# stm32f030f4p6-enc28j60.net
KiCad netlist of a schematic drawn in EAGLE
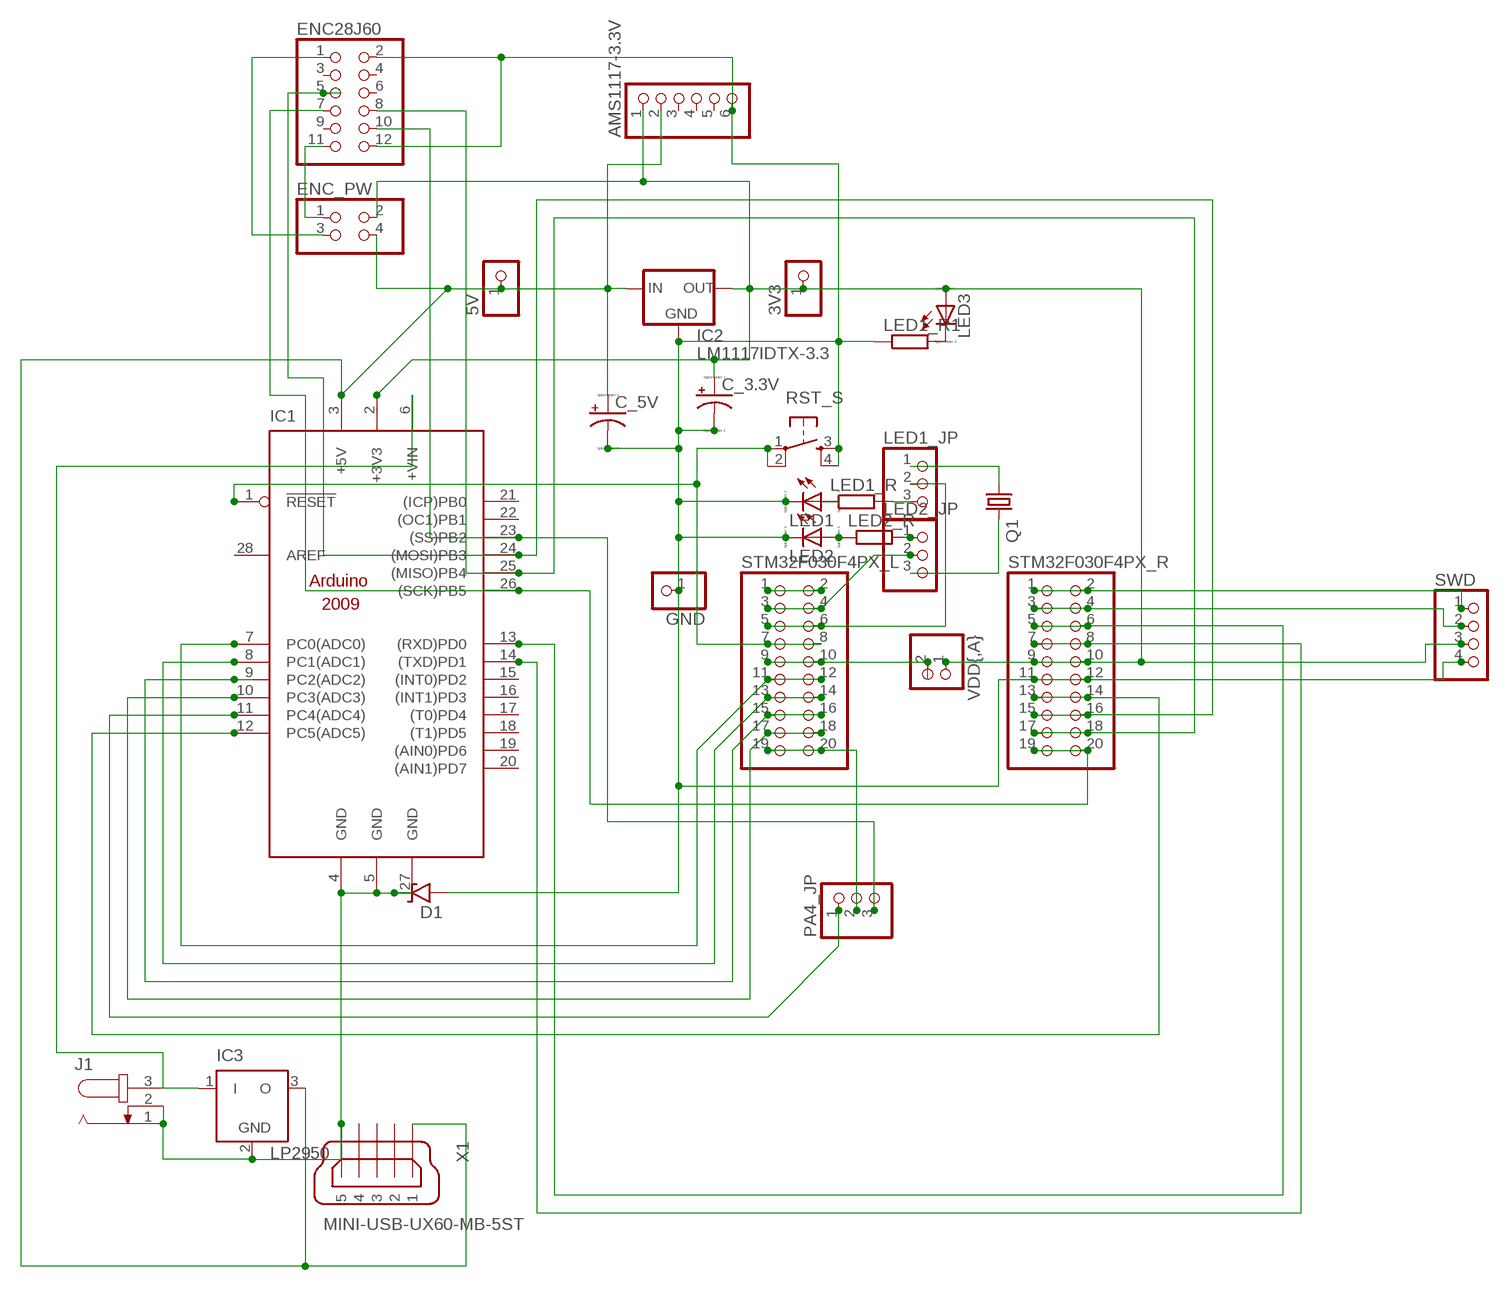
[diagram p0: schematic, sheet 1]

(export (version "E")
  (design (tool "Eeschema 10.0.6"))
  (components
    (comp (ref "3V3")
      (value "PINHD-1X1_2.00")
      (footprint "eagle-import:1X01M")
      (libsource (lib "eagle-import") (part "PINHD-1X1_2.00"))
    )
    (comp (ref "5V")
      (value "PINHD-1X1_2.00")
      (footprint "eagle-import:1X01M")
      (libsource (lib "eagle-import") (part "PINHD-1X1_2.00"))
    )
    (comp (ref "AMS1117-3.3V")
      (value "PINHD-1X06_2.54")
      (footprint "eagle-import:1X06")
      (libsource (lib "eagle-import") (part "PINHD-1X06_2.54"))
    )
    (comp (ref "C_3.3V")
      (value "CPOL-USE3.5-8")
      (footprint "eagle-import:E3,5-8")
      (libsource (lib "eagle-import") (part "CPOL-USE3.5-8"))
    )
    (comp (ref "C_5V")
      (value "CPOL-USE3.5-8")
      (footprint "eagle-import:E3,5-8")
      (libsource (lib "eagle-import") (part "CPOL-USE3.5-8"))
    )
    (comp (ref "D1")
      (value "1N9ZENER2")
      (footprint "eagle-import:DO35-2")
      (libsource (lib "eagle-import") (part "1N9ZENER2"))
    )
    (comp (ref "ENC28J60")
      (value "PINHD-2X6_2.54")
      (footprint "eagle-import:2X06")
      (libsource (lib "eagle-import") (part "PINHD-2X6_2.54"))
    )
    (comp (ref "ENC_PW")
      (value "PINHD-2X2_2.54")
      (footprint "eagle-import:2X02")
      (libsource (lib "eagle-import") (part "PINHD-2X2_2.54"))
    )
    (comp (ref "GND")
      (value "PINHD-1X1_2.00")
      (footprint "eagle-import:1X01M")
      (libsource (lib "eagle-import") (part "PINHD-1X1_2.00"))
    )
    (comp (ref "IC1")
      (value "ARDUINO2009_PIN_12")
      (footprint "eagle-import:ARDUINO2009_2")
      (libsource (lib "eagle-import") (part "ARDUINO2009_PIN_12"))
    )
    (comp (ref "IC2")
      (value "LM1117IDTX-3.3")
      (footprint "eagle-import:TO252")
      (libsource (lib "eagle-import") (part "LM1117IDTX-3.3"))
    )
    (comp (ref "IC3")
      (value "LP2950")
      (footprint "eagle-import:DPACK")
      (libsource (lib "eagle-import") (part "LP2950"))
    )
    (comp (ref "J1")
      (value "JACK-PLUG0")
      (footprint "eagle-import:SPC4077")
      (libsource (lib "eagle-import") (part "JACK-PLUG0"))
    )
    (comp (ref "LED1")
      (value "LED_ELD260")
      (footprint "eagle-import:LED_LD260")
      (libsource (lib "eagle-import") (part "LED_ELD260"))
    )
    (comp (ref "LED1_JP")
      (value "PINHD-1X3_2.54")
      (footprint "eagle-import:1X03")
      (libsource (lib "eagle-import") (part "PINHD-1X3_2.54"))
    )
    (comp (ref "LED1_R")
      (value "R-EU_0204/7")
      (footprint "eagle-import:0204_7")
      (libsource (lib "eagle-import") (part "R-EU_0204/7"))
    )
    (comp (ref "LED1_R1")
      (value "R-EU_0204/7")
      (footprint "eagle-import:0204_7")
      (libsource (lib "eagle-import") (part "R-EU_0204/7"))
    )
    (comp (ref "LED2")
      (value "LED_ELD260")
      (footprint "eagle-import:LED_LD260")
      (libsource (lib "eagle-import") (part "LED_ELD260"))
    )
    (comp (ref "LED2_JP")
      (value "PINHD-1X3_2.54")
      (footprint "eagle-import:1X03")
      (libsource (lib "eagle-import") (part "PINHD-1X3_2.54"))
    )
    (comp (ref "LED2_R")
      (value "R-EU_0204/7")
      (footprint "eagle-import:0204_7")
      (libsource (lib "eagle-import") (part "R-EU_0204/7"))
    )
    (comp (ref "LED3")
      (value "LED_ELD260")
      (footprint "eagle-import:LED_LD260")
      (libsource (lib "eagle-import") (part "LED_ELD260"))
    )
    (comp (ref "PA4_JP")
      (value "PINHD-1X3_2.54")
      (footprint "eagle-import:1X03")
      (libsource (lib "eagle-import") (part "PINHD-1X3_2.54"))
    )
    (comp (ref "Q1")
      (value "CRYSTALHC49S")
      (footprint "eagle-import:HC49_S")
      (libsource (lib "eagle-import") (part "CRYSTALHC49S"))
    )
    (comp (ref "RST_S")
      (value "TAC_SWITCHPTH")
      (footprint "eagle-import:TACTILE-PTH")
      (libsource (lib "eagle-import") (part "TAC_SWITCHPTH"))
    )
    (comp (ref "STM32F030F4PX_L")
      (value "PINHD-2X10")
      (footprint "eagle-import:2X10")
      (libsource (lib "eagle-import") (part "PINHD-2X10"))
    )
    (comp (ref "STM32F030F4PX_R")
      (value "PINHD-2X10")
      (footprint "eagle-import:2X10")
      (libsource (lib "eagle-import") (part "PINHD-2X10"))
    )
    (comp (ref "SWD")
      (value "PINHD-1X4")
      (footprint "eagle-import:1X04")
      (libsource (lib "eagle-import") (part "PINHD-1X4"))
    )
    (comp (ref "VDD{,A}")
      (value "PINHD-1X2")
      (footprint "eagle-import:1X02")
      (libsource (lib "eagle-import") (part "PINHD-1X2"))
    )
    (comp (ref "X1")
      (value "MINI-USB-UX60-MB-5ST")
      (footprint "eagle-import:UX60-MB-5ST")
      (libsource (lib "eagle-import") (part "MINI-USB-UX60-MB-5ST"))
    )
  )
  (nets
    (net (code "1") (name "Net-(ENC28J60-Pad1)") (class "Default")
      (node (ref "ENC28J60") (pin "1") (pinfunction "1_1") (pintype "passive"))
      (node (ref "ENC_PW") (pin "3") (pinfunction "3_3") (pintype "passive"))
    )
    (net (code "2") (name "Net-(ENC28J60-Pad11)") (class "Default")
      (node (ref "ENC28J60") (pin "11") (pinfunction "11_11") (pintype "passive"))
      (node (ref "ENC_PW") (pin "1") (pinfunction "1_1") (pintype "passive"))
    )
    (net (code "3") (name "Net-(IC1-(MISO)PB4)") (class "Default")
      (node (ref "ENC28J60") (pin "8") (pinfunction "8_8") (pintype "passive"))
      (node (ref "IC1") (pin "25") (pinfunction "(MISO)PB4_25") (pintype "bidirectional"))
      (node (ref "STM32F030F4PX_R") (pin "17") (pinfunction "17_17") (pintype "passive"))
      (node (ref "STM32F030F4PX_R") (pin "18") (pinfunction "18_18") (pintype "passive"))
    )
    (net (code "4") (name "Net-(IC1-(MOSI)PB3)") (class "Default")
      (node (ref "ENC28J60") (pin "5") (pinfunction "5_5") (pintype "passive"))
      (node (ref "IC1") (pin "24") (pinfunction "(MOSI)PB3_24") (pintype "bidirectional"))
      (node (ref "STM32F030F4PX_R") (pin "15") (pinfunction "15_15") (pintype "passive"))
      (node (ref "STM32F030F4PX_R") (pin "16") (pinfunction "16_16") (pintype "passive"))
    )
    (net (code "5") (name "Net-(IC1-(RXD)PD0)") (class "Default")
      (node (ref "IC1") (pin "13") (pinfunction "(RXD)PD0_13") (pintype "bidirectional"))
      (node (ref "STM32F030F4PX_R") (pin "5") (pinfunction "5_5") (pintype "passive"))
      (node (ref "STM32F030F4PX_R") (pin "6") (pinfunction "6_6") (pintype "passive"))
    )
    (net (code "6") (name "Net-(IC1-(SCK)PB5)") (class "Default")
      (node (ref "ENC28J60") (pin "7") (pinfunction "7_7") (pintype "passive"))
      (node (ref "IC1") (pin "26") (pinfunction "(SCK)PB5_26") (pintype "bidirectional"))
      (node (ref "STM32F030F4PX_R") (pin "19") (pinfunction "19_19") (pintype "passive"))
      (node (ref "STM32F030F4PX_R") (pin "20") (pinfunction "20_20") (pintype "passive"))
    )
    (net (code "7") (name "Net-(IC1-(SS)PB2)") (class "Default")
      (node (ref "ENC28J60") (pin "10") (pinfunction "10_10") (pintype "passive"))
      (node (ref "IC1") (pin "23") (pinfunction "(SS)PB2_23") (pintype "bidirectional"))
      (node (ref "PA4_JP") (pin "3") (pinfunction "3_3") (pintype "passive"))
    )
    (net (code "8") (name "Net-(IC1-(TXD)PD1)") (class "Default")
      (node (ref "IC1") (pin "14") (pinfunction "(TXD)PD1_14") (pintype "bidirectional"))
      (node (ref "STM32F030F4PX_R") (pin "7") (pinfunction "7_7") (pintype "passive"))
      (node (ref "STM32F030F4PX_R") (pin "8") (pinfunction "8_8") (pintype "passive"))
    )
    (net (code "9") (name "Net-(IC1-+3V3)") (class "Default")
      (node (ref "3V3") (pin "1") (pinfunction "1_1") (pintype "passive"))
      (node (ref "AMS1117-3.3V") (pin "1") (pinfunction "1_1") (pintype "passive"))
      (node (ref "C_3.3V") (pin "+") (pinfunction "+_+") (pintype "passive"))
      (node (ref "ENC_PW") (pin "2") (pinfunction "2_2") (pintype "passive"))
      (node (ref "IC1") (pin "2") (pinfunction "+3V3_2") (pintype "power_in"))
      (node (ref "IC2") (pin "TAB") (pinfunction "OUT_TAB") (pintype "passive"))
      (node (ref "LED3") (pin "A") (pinfunction "A_A") (pintype "passive"))
      (node (ref "STM32F030F4PX_R") (pin "10") (pinfunction "10_10") (pintype "passive"))
      (node (ref "STM32F030F4PX_R") (pin "9") (pinfunction "9_9") (pintype "passive"))
      (node (ref "SWD") (pin "3") (pinfunction "3_3") (pintype "passive"))
      (node (ref "VDD{,A}") (pin "1") (pinfunction "1_1") (pintype "passive"))
    )
    (net (code "10") (name "Net-(IC1-+5V)") (class "Default")
      (node (ref "5V") (pin "1") (pinfunction "1_1") (pintype "passive"))
      (node (ref "AMS1117-3.3V") (pin "2") (pinfunction "2_2") (pintype "passive"))
      (node (ref "C_5V") (pin "+") (pinfunction "+_+") (pintype "passive"))
      (node (ref "ENC_PW") (pin "4") (pinfunction "4_4") (pintype "passive"))
      (node (ref "IC1") (pin "3") (pinfunction "+5V_3") (pintype "power_in"))
      (node (ref "IC2") (pin "2") (pinfunction "IN_2") (pintype "input"))
      (node (ref "IC3") (pin "3") (pinfunction "O_3") (pintype "input"))
      (node (ref "X1") (pin "1") (pinfunction "1_1") (pintype "input"))
    )
    (net (code "11") (name "Net-(IC1-+VIN)") (class "Default")
      (node (ref "IC1") (pin "6") (pinfunction "+VIN_6") (pintype "bidirectional"))
      (node (ref "IC3") (pin "1") (pinfunction "I_1") (pintype "input"))
      (node (ref "J1") (pin "3") (pinfunction "3_3") (pintype "passive"))
    )
    (net (code "12") (name "Net-(IC1-PC0(ADC0))") (class "Default")
      (node (ref "IC1") (pin "7") (pinfunction "PC0(ADC0)_7") (pintype "bidirectional"))
      (node (ref "STM32F030F4PX_L") (pin "11") (pinfunction "11_11") (pintype "passive"))
      (node (ref "STM32F030F4PX_L") (pin "12") (pinfunction "12_12") (pintype "passive"))
    )
    (net (code "13") (name "Net-(IC1-PC1(ADC1))") (class "Default")
      (node (ref "IC1") (pin "8") (pinfunction "PC1(ADC1)_8") (pintype "bidirectional"))
      (node (ref "STM32F030F4PX_L") (pin "13") (pinfunction "13_13") (pintype "passive"))
      (node (ref "STM32F030F4PX_L") (pin "14") (pinfunction "14_14") (pintype "passive"))
    )
    (net (code "14") (name "Net-(IC1-PC2(ADC2))") (class "Default")
      (node (ref "IC1") (pin "9") (pinfunction "PC2(ADC2)_9") (pintype "bidirectional"))
      (node (ref "STM32F030F4PX_L") (pin "15") (pinfunction "15_15") (pintype "passive"))
      (node (ref "STM32F030F4PX_L") (pin "16") (pinfunction "16_16") (pintype "passive"))
    )
    (net (code "15") (name "Net-(IC1-PC3(ADC3))") (class "Default")
      (node (ref "IC1") (pin "10") (pinfunction "PC3(ADC3)_10") (pintype "bidirectional"))
      (node (ref "STM32F030F4PX_L") (pin "17") (pinfunction "17_17") (pintype "passive"))
      (node (ref "STM32F030F4PX_L") (pin "18") (pinfunction "18_18") (pintype "passive"))
    )
    (net (code "16") (name "Net-(IC1-PC4(ADC4))") (class "Default")
      (node (ref "IC1") (pin "11") (pinfunction "PC4(ADC4)_11") (pintype "bidirectional"))
      (node (ref "PA4_JP") (pin "1") (pinfunction "1_1") (pintype "passive"))
    )
    (net (code "17") (name "Net-(IC1-PC5(ADC5))") (class "Default")
      (node (ref "IC1") (pin "12") (pinfunction "PC5(ADC5)_12") (pintype "bidirectional"))
      (node (ref "STM32F030F4PX_R") (pin "13") (pinfunction "13_13") (pintype "passive"))
      (node (ref "STM32F030F4PX_R") (pin "14") (pinfunction "14_14") (pintype "passive"))
    )
    (net (code "18") (name "Net-(IC1-~{RESET})") (class "Default")
      (node (ref "IC1") (pin "1") (pinfunction "~{RESET}_1") (pintype "bidirectional"))
      (node (ref "RST_S") (pin "1") (pinfunction "1_1") (pintype "passive"))
      (node (ref "RST_S") (pin "2") (pinfunction "2_2") (pintype "passive"))
      (node (ref "STM32F030F4PX_L") (pin "7") (pinfunction "7_7") (pintype "passive"))
      (node (ref "STM32F030F4PX_L") (pin "8") (pinfunction "8_8") (pintype "passive"))
    )
    (net (code "19") (name "Net-(IC2-GND)") (class "Default")
      (node (ref "AMS1117-3.3V") (pin "6") (pinfunction "6_6") (pintype "passive"))
      (node (ref "C_3.3V") (pin "-") (pinfunction "-_-") (pintype "passive"))
      (node (ref "C_5V") (pin "-") (pinfunction "-_-") (pintype "passive"))
      (node (ref "D1") (pin "A") (pinfunction "A_A") (pintype "passive"))
      (node (ref "ENC28J60") (pin "12") (pinfunction "12_12") (pintype "passive"))
      (node (ref "ENC28J60") (pin "2") (pinfunction "2_2") (pintype "passive"))
      (node (ref "GND") (pin "1") (pinfunction "1_1") (pintype "passive"))
      (node (ref "IC2") (pin "1") (pinfunction "GND_1") (pintype "input"))
      (node (ref "LED1") (pin "K") (pinfunction "C_K") (pintype "passive"))
      (node (ref "LED1_R1") (pin "1") (pinfunction "1_1") (pintype "passive"))
      (node (ref "LED2") (pin "K") (pinfunction "C_K") (pintype "passive"))
      (node (ref "RST_S") (pin "3") (pinfunction "3_3") (pintype "passive"))
      (node (ref "RST_S") (pin "4") (pinfunction "4_4") (pintype "passive"))
      (node (ref "STM32F030F4PX_R") (pin "11") (pinfunction "11_11") (pintype "passive"))
      (node (ref "STM32F030F4PX_R") (pin "12") (pinfunction "12_12") (pintype "passive"))
      (node (ref "SWD") (pin "4") (pinfunction "4_4") (pintype "passive"))
    )
    (net (code "20") (name "Net-(IC3-GND)") (class "Default")
      (node (ref "D1") (pin "C") (pinfunction "C_C") (pintype "passive"))
      (node (ref "IC1") (pin "27") (pinfunction "GND_27") (pintype "power_in"))
      (node (ref "IC1") (pin "4") (pinfunction "GND_4") (pintype "power_in"))
      (node (ref "IC1") (pin "5") (pinfunction "GND_5") (pintype "power_in"))
      (node (ref "IC3") (pin "2") (pinfunction "GND_2") (pintype "power_in"))
      (node (ref "J1") (pin "1") (pinfunction "1_1") (pintype "passive"))
      (node (ref "J1") (pin "2") (pinfunction "2_2") (pintype "passive"))
      (node (ref "X1") (pin "5") (pinfunction "5_5") (pintype "input"))
    )
    (net (code "21") (name "Net-(LED1-PadA)") (class "Default")
      (node (ref "LED1") (pin "A") (pinfunction "A_A") (pintype "passive"))
      (node (ref "LED1_R") (pin "1") (pinfunction "1_1") (pintype "passive"))
    )
    (net (code "22") (name "Net-(LED1_JP-Pad1)") (class "Default")
      (node (ref "LED1_JP") (pin "1") (pinfunction "1_1") (pintype "passive"))
      (node (ref "Q1") (pin "1") (pinfunction "1_1") (pintype "passive"))
    )
    (net (code "23") (name "Net-(LED1_JP-Pad2)") (class "Default")
      (node (ref "LED1_JP") (pin "2") (pinfunction "2_2") (pintype "passive"))
      (node (ref "STM32F030F4PX_L") (pin "5") (pinfunction "5_5") (pintype "passive"))
      (node (ref "STM32F030F4PX_L") (pin "6") (pinfunction "6_6") (pintype "passive"))
    )
    (net (code "24") (name "Net-(LED1_JP-Pad3)") (class "Default")
      (node (ref "LED1_JP") (pin "3") (pinfunction "3_3") (pintype "passive"))
      (node (ref "LED1_R") (pin "2") (pinfunction "2_2") (pintype "passive"))
    )
    (net (code "25") (name "Net-(LED2-PadA)") (class "Default")
      (node (ref "LED2") (pin "A") (pinfunction "A_A") (pintype "passive"))
      (node (ref "LED2_R") (pin "1") (pinfunction "1_1") (pintype "passive"))
    )
    (net (code "26") (name "Net-(LED2_JP-Pad1)") (class "Default")
      (node (ref "LED2_JP") (pin "1") (pinfunction "1_1") (pintype "passive"))
      (node (ref "LED2_R") (pin "2") (pinfunction "2_2") (pintype "passive"))
    )
    (net (code "27") (name "Net-(LED2_JP-Pad2)") (class "Default")
      (node (ref "LED2_JP") (pin "2") (pinfunction "2_2") (pintype "passive"))
      (node (ref "STM32F030F4PX_L") (pin "3") (pinfunction "3_3") (pintype "passive"))
      (node (ref "STM32F030F4PX_L") (pin "4") (pinfunction "4_4") (pintype "passive"))
    )
    (net (code "28") (name "Net-(LED2_JP-Pad3)") (class "Default")
      (node (ref "LED2_JP") (pin "3") (pinfunction "3_3") (pintype "passive"))
      (node (ref "Q1") (pin "2") (pinfunction "2_2") (pintype "passive"))
    )
    (net (code "29") (name "Net-(LED3-C)") (class "Default")
      (node (ref "LED1_R1") (pin "2") (pinfunction "2_2") (pintype "passive"))
      (node (ref "LED3") (pin "K") (pinfunction "C_K") (pintype "passive"))
    )
    (net (code "30") (name "Net-(PA4_JP-Pad2)") (class "Default")
      (node (ref "PA4_JP") (pin "2") (pinfunction "2_2") (pintype "passive"))
      (node (ref "STM32F030F4PX_L") (pin "19") (pinfunction "19_19") (pintype "passive"))
      (node (ref "STM32F030F4PX_L") (pin "20") (pinfunction "20_20") (pintype "passive"))
    )
    (net (code "31") (name "Net-(STM32F030F4PX_L-Pad1)") (class "Default")
      (node (ref "STM32F030F4PX_L") (pin "1") (pinfunction "1_1") (pintype "passive"))
      (node (ref "STM32F030F4PX_L") (pin "2") (pinfunction "2_2") (pintype "passive"))
    )
    (net (code "32") (name "Net-(STM32F030F4PX_L-Pad10)") (class "Default")
      (node (ref "STM32F030F4PX_L") (pin "10") (pinfunction "10_10") (pintype "passive"))
      (node (ref "STM32F030F4PX_L") (pin "9") (pinfunction "9_9") (pintype "passive"))
      (node (ref "VDD{,A}") (pin "2") (pinfunction "2_2") (pintype "passive"))
    )
    (net (code "33") (name "Net-(STM32F030F4PX_R-Pad1)") (class "Default")
      (node (ref "STM32F030F4PX_R") (pin "1") (pinfunction "1_1") (pintype "passive"))
      (node (ref "STM32F030F4PX_R") (pin "2") (pinfunction "2_2") (pintype "passive"))
      (node (ref "SWD") (pin "1") (pinfunction "1_1") (pintype "passive"))
    )
    (net (code "34") (name "Net-(STM32F030F4PX_R-Pad3)") (class "Default")
      (node (ref "STM32F030F4PX_R") (pin "3") (pinfunction "3_3") (pintype "passive"))
      (node (ref "STM32F030F4PX_R") (pin "4") (pinfunction "4_4") (pintype "passive"))
      (node (ref "SWD") (pin "2") (pinfunction "2_2") (pintype "passive"))
    )
    (net (code "35") (name "unconnected-(AMS1117-3.3V-Pad3)") (class "Default")
      (node (ref "AMS1117-3.3V") (pin "3") (pinfunction "3_3") (pintype "passive"))
    )
    (net (code "36") (name "unconnected-(AMS1117-3.3V-Pad4)") (class "Default")
      (node (ref "AMS1117-3.3V") (pin "4") (pinfunction "4_4") (pintype "passive"))
    )
    (net (code "37") (name "unconnected-(AMS1117-3.3V-Pad5)") (class "Default")
      (node (ref "AMS1117-3.3V") (pin "5") (pinfunction "5_5") (pintype "passive"))
    )
    (net (code "38") (name "unconnected-(ENC28J60-Pad3)") (class "Default")
      (node (ref "ENC28J60") (pin "3") (pinfunction "3_3") (pintype "passive"))
    )
    (net (code "39") (name "unconnected-(ENC28J60-Pad4)") (class "Default")
      (node (ref "ENC28J60") (pin "4") (pinfunction "4_4") (pintype "passive"))
    )
    (net (code "40") (name "unconnected-(ENC28J60-Pad6)") (class "Default")
      (node (ref "ENC28J60") (pin "6") (pinfunction "6_6") (pintype "passive"))
    )
    (net (code "41") (name "unconnected-(ENC28J60-Pad9)") (class "Default")
      (node (ref "ENC28J60") (pin "9") (pinfunction "9_9") (pintype "passive"))
    )
    (net (code "42") (name "unconnected-(IC1-(AIN0)PD6-Pad19)") (class "Default")
      (node (ref "IC1") (pin "19") (pinfunction "(AIN0)PD6_19") (pintype "bidirectional"))
    )
    (net (code "43") (name "unconnected-(IC1-(AIN1)PD7-Pad20)") (class "Default")
      (node (ref "IC1") (pin "20") (pinfunction "(AIN1)PD7_20") (pintype "bidirectional"))
    )
    (net (code "44") (name "unconnected-(IC1-(ICP)PB0-Pad21)") (class "Default")
      (node (ref "IC1") (pin "21") (pinfunction "(ICP)PB0_21") (pintype "bidirectional"))
    )
    (net (code "45") (name "unconnected-(IC1-(INT0)PD2-Pad15)") (class "Default")
      (node (ref "IC1") (pin "15") (pinfunction "(INT0)PD2_15") (pintype "bidirectional"))
    )
    (net (code "46") (name "unconnected-(IC1-(INT1)PD3-Pad16)") (class "Default")
      (node (ref "IC1") (pin "16") (pinfunction "(INT1)PD3_16") (pintype "bidirectional"))
    )
    (net (code "47") (name "unconnected-(IC1-(OC1)PB1-Pad22)") (class "Default")
      (node (ref "IC1") (pin "22") (pinfunction "(OC1)PB1_22") (pintype "bidirectional"))
    )
    (net (code "48") (name "unconnected-(IC1-(T0)PD4-Pad17)") (class "Default")
      (node (ref "IC1") (pin "17") (pinfunction "(T0)PD4_17") (pintype "bidirectional"))
    )
    (net (code "49") (name "unconnected-(IC1-(T1)PD5-Pad18)") (class "Default")
      (node (ref "IC1") (pin "18") (pinfunction "(T1)PD5_18") (pintype "bidirectional"))
    )
    (net (code "50") (name "unconnected-(IC1-AREF-Pad28)") (class "Default")
      (node (ref "IC1") (pin "28") (pinfunction "AREF_28") (pintype "bidirectional"))
    )
    (net (code "51") (name "unconnected-(X1-Pad2)") (class "Default")
      (node (ref "X1") (pin "2") (pinfunction "2_2") (pintype "input"))
    )
    (net (code "52") (name "unconnected-(X1-Pad3)") (class "Default")
      (node (ref "X1") (pin "3") (pinfunction "3_3") (pintype "input"))
    )
    (net (code "53") (name "unconnected-(X1-Pad4)") (class "Default")
      (node (ref "X1") (pin "4") (pinfunction "4_4") (pintype "input"))
    )
  )
)
